# Breakout_UVB.net
KiCad netlist of a schematic drawn in EAGLE
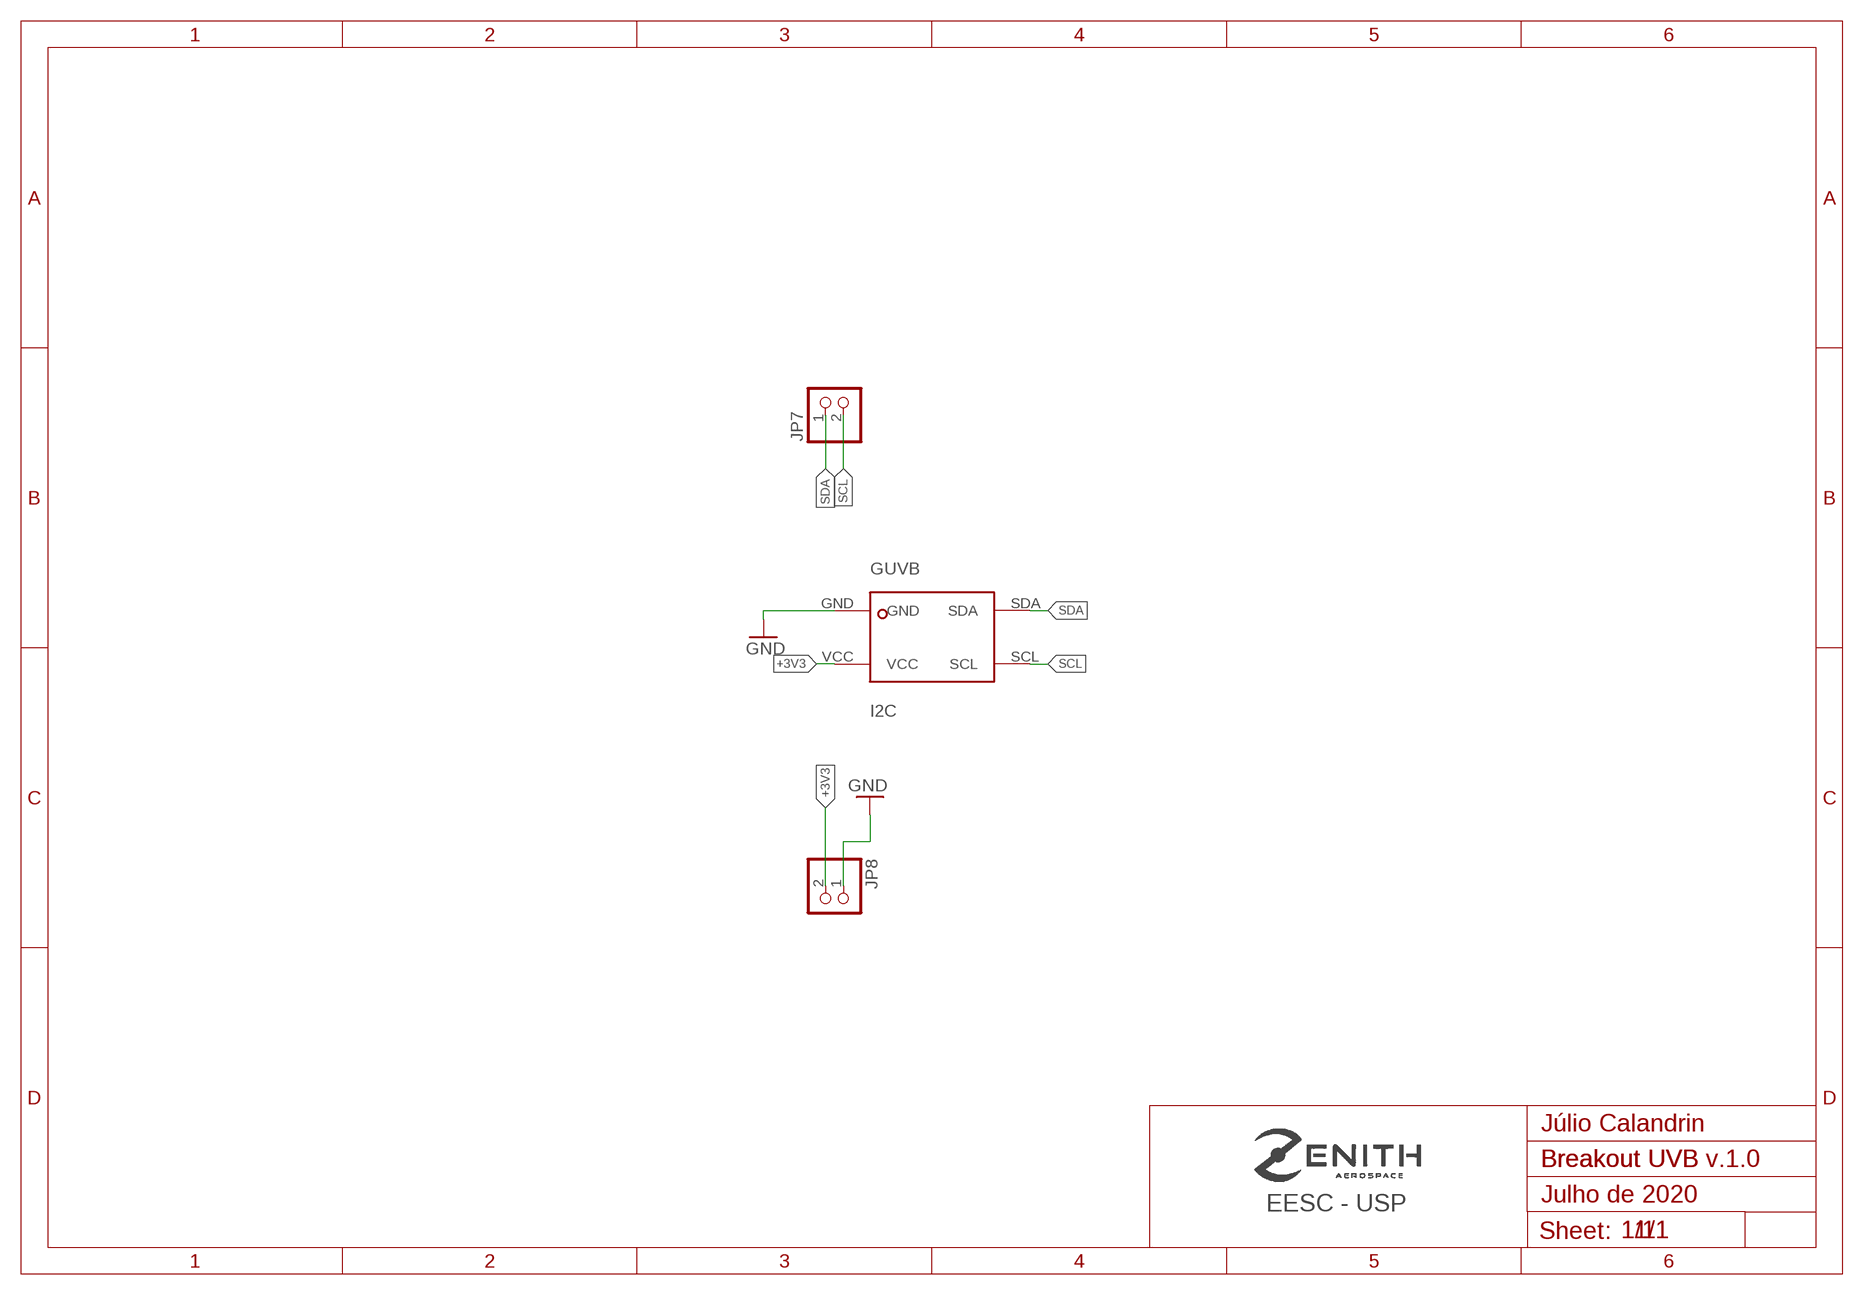
[diagram p0: schematic, sheet 1]

(export (version "E")
  (design (tool "Eeschema 10.0.6"))
  (components
    (comp (ref "GUVB")
      (value "I2C")
      (footprint "eagle-import:GUV_A_B")
      (libsource (lib "eagle-import") (part "GUVB-C31SM"))
    )
    (comp (ref "JP7")
      (value "PINHD-1X2")
      (footprint "eagle-import:1X02(PAD_REDUZIDO)")
      (libsource (lib "eagle-import") (part "PINHD-1X2"))
    )
    (comp (ref "JP8")
      (value "PINHD-1X2")
      (footprint "eagle-import:1X02(PAD_REDUZIDO)")
      (libsource (lib "eagle-import") (part "PINHD-1X2"))
    )
  )
  (nets
    (net (code "1") (name "+3V3") (class "Default")
      (node (ref "GUVB") (pin "VCC") (pinfunction "VCC_VCC") (pintype "bidirectional"))
      (node (ref "JP8") (pin "2") (pinfunction "2_2") (pintype "passive"))
    )
    (net (code "2") (name "GND") (class "Default")
      (node (ref "GUVB") (pin "GND") (pinfunction "GND_GND") (pintype "bidirectional"))
      (node (ref "JP8") (pin "1") (pinfunction "1_1") (pintype "passive"))
    )
    (net (code "3") (name "SCL") (class "Default")
      (node (ref "GUVB") (pin "SCL") (pinfunction "SCL_SCL") (pintype "bidirectional"))
      (node (ref "JP7") (pin "2") (pinfunction "2_2") (pintype "passive"))
    )
    (net (code "4") (name "SDA") (class "Default")
      (node (ref "GUVB") (pin "SDA") (pinfunction "SDA_SDA") (pintype "bidirectional"))
      (node (ref "JP7") (pin "1") (pinfunction "1_1") (pintype "passive"))
    )
  )
)
